# Teensy_3_2_Schematic.net
KiCad netlist of a schematic drawn in Altium Designer
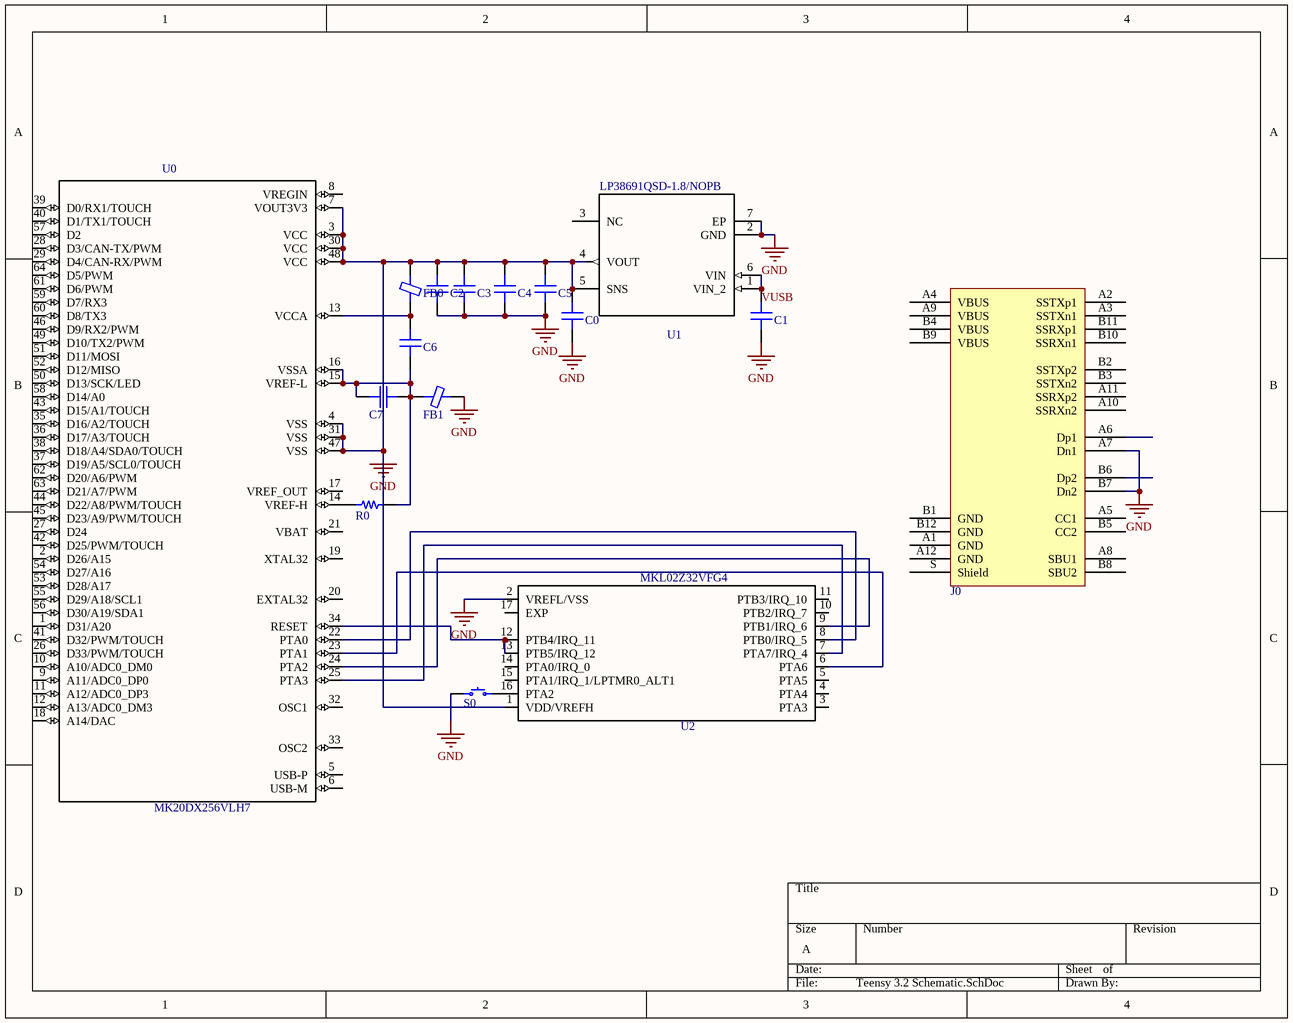
[diagram p0: Teensy 3.2 Schematic.SchDoc]

(export (version "E")
  (design (tool "Eeschema 10.0.6"))
  (components
    (comp (ref "C0")
      (value "2.2uF")
      (footprint "CAP 0201/0603")
      (description "CAP CER 2.2UF 10V X5R 0201")
      (fields
        (field (name "PART NUMBER") "GRM033R61A225KE47D")
        (field (name "MANUFACTURER") "Murata Electronics North America")
      )
      (libsource (lib "Celestial Library Database") (part "Capacitor"))
    )
    (comp (ref "C1")
      (value "2.2uF")
      (footprint "CAP 0201/0603")
      (description "CAP CER 2.2UF 10V X5R 0201")
      (fields
        (field (name "PART NUMBER") "GRM033R61A225KE47D")
        (field (name "MANUFACTURER") "Murata Electronics North America")
      )
      (libsource (lib "Celestial Library Database") (part "Capacitor"))
    )
    (comp (ref "C2")
      (value "2.2uF")
      (footprint "CAP 0201/0603")
      (description "CAP CER 2.2UF 10V X5R 0201")
      (fields
        (field (name "PART NUMBER") "GRM033R61A225KE47D")
        (field (name "MANUFACTURER") "Murata Electronics North America")
      )
      (libsource (lib "Celestial Library Database") (part "Capacitor"))
    )
    (comp (ref "C3")
      (value "0.1uF")
      (footprint "CAP 0402/1005")
      (description "CAP CER 0.1UF 6.3V X7R 0402")
      (fields
        (field (name "PART NUMBER") "GRM155R70J104KA01D")
        (field (name "MANUFACTURER") "Murata Electronics North America")
      )
      (libsource (lib "Celestial Library Database") (part "Capacitor"))
    )
    (comp (ref "C4")
      (value "0.1uF")
      (footprint "CAP 0402/1005")
      (description "CAP CER 0.1UF 6.3V X7R 0402")
      (fields
        (field (name "PART NUMBER") "GRM155R70J104KA01D")
        (field (name "MANUFACTURER") "Murata Electronics North America")
      )
      (libsource (lib "Celestial Library Database") (part "Capacitor"))
    )
    (comp (ref "C5")
      (value "0.1uF")
      (footprint "CAP 0402/1005")
      (description "CAP CER 0.1UF 6.3V X7R 0402")
      (fields
        (field (name "PART NUMBER") "GRM155R70J104KA01D")
        (field (name "MANUFACTURER") "Murata Electronics North America")
      )
      (libsource (lib "Celestial Library Database") (part "Capacitor"))
    )
    (comp (ref "C6")
      (value "2.2uF")
      (footprint "CAP 0201/0603")
      (description "CAP CER 2.2UF 10V X5R 0201")
      (fields
        (field (name "PART NUMBER") "GRM033R61A225KE47D")
        (field (name "MANUFACTURER") "Murata Electronics North America")
      )
      (libsource (lib "Celestial Library Database") (part "Capacitor"))
    )
    (comp (ref "C7")
      (value "0.1uF")
      (footprint "CAP 0402/1005")
      (description "CAP CER 0.1UF 6.3V X7R 0402")
      (fields
        (field (name "PART NUMBER") "GRM155R70J104KA01D")
        (field (name "MANUFACTURER") "Murata Electronics North America")
      )
      (libsource (lib "Celestial Library Database") (part "Capacitor"))
    )
    (comp (ref "FB0")
      (value "600 Ohm @ 100MHz")
      (footprint "FER 0201/0603")
      (description "FERRITE BEAD 600 OHM 0201 1LN")
      (fields
        (field (name "PART NUMBER") "BLM03AX601SN1D")
        (field (name "MANUFACTURER") "Murata Electronics North America")
      )
      (libsource (lib "Celestial Library Database") (part "Ferrite Chip"))
    )
    (comp (ref "FB1")
      (value "600 Ohm @ 100MHz")
      (footprint "FER 0201/0603")
      (description "FERRITE BEAD 600 OHM 0201 1LN")
      (fields
        (field (name "PART NUMBER") "BLM03AX601SN1D")
        (field (name "MANUFACTURER") "Murata Electronics North America")
      )
      (libsource (lib "Celestial Library Database") (part "Ferrite Chip"))
    )
    (comp (ref "J0")
      (value "USB C")
      (footprint "TE USB-C 2129691-1")
      (description "USB 3.1 TYPE C MID MOUNT HYBRID")
      (fields
        (field (name "PART NUMBER") "2129691-1")
        (field (name "MANUFACTURER") "TE Connectivity AMP Connectors")
      )
      (libsource (lib "Celestial Library Database") (part "USB 3.0 Type C"))
    )
    (comp (ref "R0")
      (value "470")
      (footprint "RES 0402/1005")
      (description "RES SMD 470 OHM 1% 1/10W 0402")
      (fields
        (field (name "PART NUMBER") "ERJ-2RKF4700X")
        (field (name "MANUFACTURER") "Panasonic Electronic Components")
      )
      (libsource (lib "Celestial Library Database") (part "Resistor"))
    )
    (comp (ref "S0")
      (value "FSMSMTR")
      (footprint "TE FSMSMTR")
      (description "SWITCH TACTILE SPST-NO 0.05A 24V")
      (fields (field (name "MANUFACTURER") "TE Connectivity Alcoswitch Switches"))
      (libsource (lib "Celestial Library Database") (part "SPST-NO 2 PIN"))
    )
    (comp (ref "U0")
      (value "MK20DX256VLH7")
      (footprint "QFP50P1200X1200X160-64N")
      (description "MCU 32-bit Kinetis K20 ARM Cortex M4 RISC 256KB Flash 1.8V/2.5V/3.3V 64-Pin LQFP Tray")
      (fields (field (name "MF") "NXP USA"))
      (libsource (lib "MK20DX256VLH7") (part "MK20DX256VLH7"))
    )
    (comp (ref "U1")
      (value "LP38691QSD-1.8/NOPB")
      (footprint "DFN300X300X80-7N")
      (description "500mA Low Dropout CMOS Linear egulators Stable with Ceramic Output Capacitors 6-WSON -40 to 125")
      (fields (field (name "MF") "Texas Instruments"))
      (libsource (lib "LP38691QSD-1.8_NOPB") (part "LP38691QSD-1.8/NOPB"))
    )
    (comp (ref "U2")
      (value "MKL02Z32VFG4")
      (footprint "QFN50P300X300X65-17N")
      (description "MCU 32-Bit KL02 ARM Cortex M0+ RISC 32KB Flash 1.8V/2.5V/3.3V 16-Pin QFN EP Tray")
      (fields (field (name "MF") "NXP USA"))
      (libsource (lib "MKL02Z32VFG4") (part "MKL02Z32VFG4"))
    )
  )
  (nets
    (net (code "1") (name "/VUSB") (class "Default")
      (node (ref "C1") (pin "1") (pinfunction "1_1") (pintype "passive"))
      (node (ref "U1") (pin "1") (pinfunction "VIN_2_1") (pintype "input"))
      (node (ref "U1") (pin "6") (pinfunction "VIN_6") (pintype "input"))
    )
    (net (code "2") (name "GND") (class "Default")
      (node (ref "C0") (pin "1") (pinfunction "1_1") (pintype "passive"))
      (node (ref "C0") (pin "2") (pinfunction "2_2") (pintype "passive"))
      (node (ref "C1") (pin "2") (pinfunction "2_2") (pintype "passive"))
      (node (ref "C2") (pin "1") (pinfunction "1_1") (pintype "passive"))
      (node (ref "C2") (pin "2") (pinfunction "2_2") (pintype "passive"))
      (node (ref "C3") (pin "1") (pinfunction "1_1") (pintype "passive"))
      (node (ref "C3") (pin "2") (pinfunction "2_2") (pintype "passive"))
      (node (ref "C4") (pin "1") (pinfunction "1_1") (pintype "passive"))
      (node (ref "C4") (pin "2") (pinfunction "2_2") (pintype "passive"))
      (node (ref "C5") (pin "1") (pinfunction "1_1") (pintype "passive"))
      (node (ref "C5") (pin "2") (pinfunction "2_2") (pintype "passive"))
      (node (ref "FB0") (pin "1") (pinfunction "1_1") (pintype "passive"))
      (node (ref "FB1") (pin "1") (pinfunction "1_1") (pintype "passive"))
      (node (ref "J0") (pin "A7") (pinfunction "Dn1_A7") (pintype "passive"))
      (node (ref "J0") (pin "B7") (pinfunction "Dn2_B7") (pintype "passive"))
      (node (ref "S0") (pin "1") (pinfunction "1_1") (pintype "passive"))
      (node (ref "U0") (pin "3") (pinfunction "VCC_3") (pintype "bidirectional"))
      (node (ref "U0") (pin "30") (pinfunction "VCC_30") (pintype "bidirectional"))
      (node (ref "U0") (pin "31") (pinfunction "VSS_31") (pintype "bidirectional"))
      (node (ref "U0") (pin "4") (pinfunction "VSS_4") (pintype "bidirectional"))
      (node (ref "U0") (pin "47") (pinfunction "VSS_47") (pintype "bidirectional"))
      (node (ref "U0") (pin "48") (pinfunction "VCC_48") (pintype "bidirectional"))
      (node (ref "U0") (pin "7") (pinfunction "VOUT3V3_7") (pintype "bidirectional"))
      (node (ref "U1") (pin "2") (pinfunction "GND_2") (pintype "passive"))
      (node (ref "U1") (pin "4") (pinfunction "VOUT_4") (pintype "output"))
      (node (ref "U1") (pin "5") (pinfunction "SNS_5") (pintype "passive"))
      (node (ref "U1") (pin "7") (pinfunction "EP_7") (pintype "passive"))
      (node (ref "U2") (pin "1") (pinfunction "VDD/VREFH_1") (pintype "power_in"))
      (node (ref "U2") (pin "2") (pinfunction "VREFL/VSS_2") (pintype "power_in"))
    )
    (net (code "3") (name "Net-(U0-PTA0)") (class "Default")
      (node (ref "U0") (pin "22") (pinfunction "PTA0_22") (pintype "bidirectional"))
      (node (ref "U2") (pin "8") (pinfunction "PTB0/IRQ_5_8") (pintype "bidirectional"))
    )
    (net (code "4") (name "Net-(U0-PTA1)") (class "Default")
      (node (ref "U0") (pin "23") (pinfunction "PTA1_23") (pintype "bidirectional"))
      (node (ref "U2") (pin "6") (pinfunction "PTA6_6") (pintype "bidirectional"))
    )
    (net (code "5") (name "Net-(U0-PTA2)") (class "Default")
      (node (ref "U0") (pin "24") (pinfunction "PTA2_24") (pintype "bidirectional"))
      (node (ref "U2") (pin "9") (pinfunction "PTB1/IRQ_6_9") (pintype "bidirectional"))
    )
    (net (code "6") (name "Net-(U0-PTA3)") (class "Default")
      (node (ref "U0") (pin "25") (pinfunction "PTA3_25") (pintype "bidirectional"))
      (node (ref "U2") (pin "7") (pinfunction "PTA7/IRQ_4_7") (pintype "bidirectional"))
    )
    (net (code "7") (name "Net-(U0-RESET)") (class "Default")
      (node (ref "U0") (pin "34") (pinfunction "RESET_34") (pintype "bidirectional"))
      (node (ref "U2") (pin "12") (pinfunction "PTB4/IRQ_11_12") (pintype "bidirectional"))
      (node (ref "U2") (pin "13") (pinfunction "PTB5/IRQ_12_13") (pintype "bidirectional"))
    )
    (net (code "8") (name "Net-(U0-VCCA)") (class "Default")
      (node (ref "C6") (pin "1") (pinfunction "1_1") (pintype "passive"))
      (node (ref "FB0") (pin "2") (pinfunction "2_2") (pintype "passive"))
      (node (ref "U0") (pin "13") (pinfunction "VCCA_13") (pintype "bidirectional"))
    )
    (net (code "9") (name "Net-(U0-VREF-H)") (class "Default")
      (node (ref "R0") (pin "2") (pinfunction "2_2") (pintype "passive"))
      (node (ref "U0") (pin "14") (pinfunction "VREF-H_14") (pintype "bidirectional"))
    )
    (net (code "10") (name "Net-(U0-VREF-L)") (class "Default")
      (node (ref "C6") (pin "2") (pinfunction "2_2") (pintype "passive"))
      (node (ref "C7") (pin "1") (pinfunction "1_1") (pintype "passive"))
      (node (ref "C7") (pin "2") (pinfunction "2_2") (pintype "passive"))
      (node (ref "FB1") (pin "2") (pinfunction "2_2") (pintype "passive"))
      (node (ref "R0") (pin "1") (pinfunction "1_1") (pintype "passive"))
      (node (ref "U0") (pin "15") (pinfunction "VREF-L_15") (pintype "bidirectional"))
      (node (ref "U0") (pin "16") (pinfunction "VSSA_16") (pintype "bidirectional"))
    )
    (net (code "11") (name "Net-(U2-PTA2)") (class "Default")
      (node (ref "S0") (pin "2") (pinfunction "2_2") (pintype "passive"))
      (node (ref "U2") (pin "16") (pinfunction "PTA2_16") (pintype "bidirectional"))
    )
    (net (code "12") (name "unconnected-(J0-CC1-PadA5)") (class "Default")
      (node (ref "J0") (pin "A5") (pinfunction "CC1_A5") (pintype "passive"))
    )
    (net (code "13") (name "unconnected-(J0-CC2-PadB5)") (class "Default")
      (node (ref "J0") (pin "B5") (pinfunction "CC2_B5") (pintype "passive"))
    )
    (net (code "14") (name "unconnected-(J0-Dp1-PadA6)") (class "Default")
      (node (ref "J0") (pin "A6") (pinfunction "Dp1_A6") (pintype "passive"))
    )
    (net (code "15") (name "unconnected-(J0-Dp2-PadB6)") (class "Default")
      (node (ref "J0") (pin "B6") (pinfunction "Dp2_B6") (pintype "passive"))
    )
    (net (code "16") (name "unconnected-(J0-GND-PadA1)") (class "Default")
      (node (ref "J0") (pin "A1") (pinfunction "GND_A1") (pintype "passive"))
    )
    (net (code "17") (name "unconnected-(J0-GND-PadA12)") (class "Default")
      (node (ref "J0") (pin "A12") (pinfunction "GND_A12") (pintype "passive"))
    )
    (net (code "18") (name "unconnected-(J0-GND-PadB1)") (class "Default")
      (node (ref "J0") (pin "B1") (pinfunction "GND_B1") (pintype "passive"))
    )
    (net (code "19") (name "unconnected-(J0-GND-PadB12)") (class "Default")
      (node (ref "J0") (pin "B12") (pinfunction "GND_B12") (pintype "passive"))
    )
    (net (code "20") (name "unconnected-(J0-SBU1-PadA8)") (class "Default")
      (node (ref "J0") (pin "A8") (pinfunction "SBU1_A8") (pintype "passive"))
    )
    (net (code "21") (name "unconnected-(J0-SBU2-PadB8)") (class "Default")
      (node (ref "J0") (pin "B8") (pinfunction "SBU2_B8") (pintype "passive"))
    )
    (net (code "22") (name "unconnected-(J0-SSRXn1-PadB10)") (class "Default")
      (node (ref "J0") (pin "B10") (pinfunction "SSRXn1_B10") (pintype "passive"))
    )
    (net (code "23") (name "unconnected-(J0-SSRXn2-PadA10)") (class "Default")
      (node (ref "J0") (pin "A10") (pinfunction "SSRXn2_A10") (pintype "passive"))
    )
    (net (code "24") (name "unconnected-(J0-SSRXp1-PadB11)") (class "Default")
      (node (ref "J0") (pin "B11") (pinfunction "SSRXp1_B11") (pintype "passive"))
    )
    (net (code "25") (name "unconnected-(J0-SSRXp2-PadA11)") (class "Default")
      (node (ref "J0") (pin "A11") (pinfunction "SSRXp2_A11") (pintype "passive"))
    )
    (net (code "26") (name "unconnected-(J0-SSTXn1-PadA3)") (class "Default")
      (node (ref "J0") (pin "A3") (pinfunction "SSTXn1_A3") (pintype "passive"))
    )
    (net (code "27") (name "unconnected-(J0-SSTXn2-PadB3)") (class "Default")
      (node (ref "J0") (pin "B3") (pinfunction "SSTXn2_B3") (pintype "passive"))
    )
    (net (code "28") (name "unconnected-(J0-SSTXp1-PadA2)") (class "Default")
      (node (ref "J0") (pin "A2") (pinfunction "SSTXp1_A2") (pintype "passive"))
    )
    (net (code "29") (name "unconnected-(J0-SSTXp2-PadB2)") (class "Default")
      (node (ref "J0") (pin "B2") (pinfunction "SSTXp2_B2") (pintype "passive"))
    )
    (net (code "30") (name "unconnected-(J0-Shield-PadS)") (class "Default")
      (node (ref "J0") (pin "S") (pinfunction "Shield_S") (pintype "passive"))
    )
    (net (code "31") (name "unconnected-(J0-VBUS-PadA4)") (class "Default")
      (node (ref "J0") (pin "A4") (pinfunction "VBUS_A4") (pintype "passive"))
    )
    (net (code "32") (name "unconnected-(J0-VBUS-PadA9)") (class "Default")
      (node (ref "J0") (pin "A9") (pinfunction "VBUS_A9") (pintype "passive"))
    )
    (net (code "33") (name "unconnected-(J0-VBUS-PadB4)") (class "Default")
      (node (ref "J0") (pin "B4") (pinfunction "VBUS_B4") (pintype "passive"))
    )
    (net (code "34") (name "unconnected-(J0-VBUS-PadB9)") (class "Default")
      (node (ref "J0") (pin "B9") (pinfunction "VBUS_B9") (pintype "passive"))
    )
    (net (code "35") (name "unconnected-(U0-A10{slash}ADC0_DM0-Pad10)") (class "Default")
      (node (ref "U0") (pin "10") (pinfunction "A10/ADC0_DM0_10") (pintype "bidirectional"))
    )
    (net (code "36") (name "unconnected-(U0-A11{slash}ADC0_DP0-Pad9)") (class "Default")
      (node (ref "U0") (pin "9") (pinfunction "A11/ADC0_DP0_9") (pintype "bidirectional"))
    )
    (net (code "37") (name "unconnected-(U0-A12{slash}ADC0_DP3-Pad11)") (class "Default")
      (node (ref "U0") (pin "11") (pinfunction "A12/ADC0_DP3_11") (pintype "bidirectional"))
    )
    (net (code "38") (name "unconnected-(U0-A13{slash}ADC0_DM3-Pad12)") (class "Default")
      (node (ref "U0") (pin "12") (pinfunction "A13/ADC0_DM3_12") (pintype "bidirectional"))
    )
    (net (code "39") (name "unconnected-(U0-A14{slash}DAC-Pad18)") (class "Default")
      (node (ref "U0") (pin "18") (pinfunction "A14/DAC_18") (pintype "bidirectional"))
    )
    (net (code "40") (name "unconnected-(U0-D0{slash}RX1{slash}TOUCH-Pad39)") (class "Default")
      (node (ref "U0") (pin "39") (pinfunction "D0/RX1/TOUCH_39") (pintype "bidirectional"))
    )
    (net (code "41") (name "unconnected-(U0-D1{slash}TX1{slash}TOUCH-Pad40)") (class "Default")
      (node (ref "U0") (pin "40") (pinfunction "D1/TX1/TOUCH_40") (pintype "bidirectional"))
    )
    (net (code "42") (name "unconnected-(U0-D2-Pad57)") (class "Default")
      (node (ref "U0") (pin "57") (pinfunction "D2_57") (pintype "bidirectional"))
    )
    (net (code "43") (name "unconnected-(U0-D3{slash}CAN-TX{slash}PWM-Pad28)") (class "Default")
      (node (ref "U0") (pin "28") (pinfunction "D3/CAN-TX/PWM_28") (pintype "bidirectional"))
    )
    (net (code "44") (name "unconnected-(U0-D4{slash}CAN-RX{slash}PWM-Pad29)") (class "Default")
      (node (ref "U0") (pin "29") (pinfunction "D4/CAN-RX/PWM_29") (pintype "bidirectional"))
    )
    (net (code "45") (name "unconnected-(U0-D5{slash}PWM-Pad64)") (class "Default")
      (node (ref "U0") (pin "64") (pinfunction "D5/PWM_64") (pintype "bidirectional"))
    )
    (net (code "46") (name "unconnected-(U0-D6{slash}PWM-Pad61)") (class "Default")
      (node (ref "U0") (pin "61") (pinfunction "D6/PWM_61") (pintype "bidirectional"))
    )
    (net (code "47") (name "unconnected-(U0-D7{slash}RX3-Pad59)") (class "Default")
      (node (ref "U0") (pin "59") (pinfunction "D7/RX3_59") (pintype "bidirectional"))
    )
    (net (code "48") (name "unconnected-(U0-D8{slash}TX3-Pad60)") (class "Default")
      (node (ref "U0") (pin "60") (pinfunction "D8/TX3_60") (pintype "bidirectional"))
    )
    (net (code "49") (name "unconnected-(U0-D9{slash}RX2{slash}PWM-Pad46)") (class "Default")
      (node (ref "U0") (pin "46") (pinfunction "D9/RX2/PWM_46") (pintype "bidirectional"))
    )
    (net (code "50") (name "unconnected-(U0-D10{slash}TX2{slash}PWM-Pad49)") (class "Default")
      (node (ref "U0") (pin "49") (pinfunction "D10/TX2/PWM_49") (pintype "bidirectional"))
    )
    (net (code "51") (name "unconnected-(U0-D11{slash}MOSI-Pad51)") (class "Default")
      (node (ref "U0") (pin "51") (pinfunction "D11/MOSI_51") (pintype "bidirectional"))
    )
    (net (code "52") (name "unconnected-(U0-D12{slash}MISO-Pad52)") (class "Default")
      (node (ref "U0") (pin "52") (pinfunction "D12/MISO_52") (pintype "bidirectional"))
    )
    (net (code "53") (name "unconnected-(U0-D13{slash}SCK{slash}LED-Pad50)") (class "Default")
      (node (ref "U0") (pin "50") (pinfunction "D13/SCK/LED_50") (pintype "bidirectional"))
    )
    (net (code "54") (name "unconnected-(U0-D14{slash}A0-Pad58)") (class "Default")
      (node (ref "U0") (pin "58") (pinfunction "D14/A0_58") (pintype "bidirectional"))
    )
    (net (code "55") (name "unconnected-(U0-D15{slash}A1{slash}TOUCH-Pad43)") (class "Default")
      (node (ref "U0") (pin "43") (pinfunction "D15/A1/TOUCH_43") (pintype "bidirectional"))
    )
    (net (code "56") (name "unconnected-(U0-D16{slash}A2{slash}TOUCH-Pad35)") (class "Default")
      (node (ref "U0") (pin "35") (pinfunction "D16/A2/TOUCH_35") (pintype "bidirectional"))
    )
    (net (code "57") (name "unconnected-(U0-D17{slash}A3{slash}TOUCH-Pad36)") (class "Default")
      (node (ref "U0") (pin "36") (pinfunction "D17/A3/TOUCH_36") (pintype "bidirectional"))
    )
    (net (code "58") (name "unconnected-(U0-D18{slash}A4{slash}SDA0{slash}TOUCH-Pad38)") (class "Default")
      (node (ref "U0") (pin "38") (pinfunction "D18/A4/SDA0/TOUCH_38") (pintype "bidirectional"))
    )
    (net (code "59") (name "unconnected-(U0-D19{slash}A5{slash}SCL0{slash}TOUCH-Pad37)") (class "Default")
      (node (ref "U0") (pin "37") (pinfunction "D19/A5/SCL0/TOUCH_37") (pintype "bidirectional"))
    )
    (net (code "60") (name "unconnected-(U0-D20{slash}A6{slash}PWM-Pad62)") (class "Default")
      (node (ref "U0") (pin "62") (pinfunction "D20/A6/PWM_62") (pintype "bidirectional"))
    )
    (net (code "61") (name "unconnected-(U0-D21{slash}A7{slash}PWM-Pad63)") (class "Default")
      (node (ref "U0") (pin "63") (pinfunction "D21/A7/PWM_63") (pintype "bidirectional"))
    )
    (net (code "62") (name "unconnected-(U0-D22{slash}A8{slash}PWM{slash}TOUCH-Pad44)") (class "Default")
      (node (ref "U0") (pin "44") (pinfunction "D22/A8/PWM/TOUCH_44") (pintype "bidirectional"))
    )
    (net (code "63") (name "unconnected-(U0-D23{slash}A9{slash}PWM{slash}TOUCH-Pad45)") (class "Default")
      (node (ref "U0") (pin "45") (pinfunction "D23/A9/PWM/TOUCH_45") (pintype "bidirectional"))
    )
    (net (code "64") (name "unconnected-(U0-D24-Pad27)") (class "Default")
      (node (ref "U0") (pin "27") (pinfunction "D24_27") (pintype "bidirectional"))
    )
    (net (code "65") (name "unconnected-(U0-D25{slash}PWM{slash}TOUCH-Pad42)") (class "Default")
      (node (ref "U0") (pin "42") (pinfunction "D25/PWM/TOUCH_42") (pintype "bidirectional"))
    )
    (net (code "66") (name "unconnected-(U0-D26{slash}A15-Pad2)") (class "Default")
      (node (ref "U0") (pin "2") (pinfunction "D26/A15_2") (pintype "bidirectional"))
    )
    (net (code "67") (name "unconnected-(U0-D27{slash}A16-Pad54)") (class "Default")
      (node (ref "U0") (pin "54") (pinfunction "D27/A16_54") (pintype "bidirectional"))
    )
    (net (code "68") (name "unconnected-(U0-D28{slash}A17-Pad53)") (class "Default")
      (node (ref "U0") (pin "53") (pinfunction "D28/A17_53") (pintype "bidirectional"))
    )
    (net (code "69") (name "unconnected-(U0-D29{slash}A18{slash}SCL1-Pad55)") (class "Default")
      (node (ref "U0") (pin "55") (pinfunction "D29/A18/SCL1_55") (pintype "bidirectional"))
    )
    (net (code "70") (name "unconnected-(U0-D30{slash}A19{slash}SDA1-Pad56)") (class "Default")
      (node (ref "U0") (pin "56") (pinfunction "D30/A19/SDA1_56") (pintype "bidirectional"))
    )
    (net (code "71") (name "unconnected-(U0-D31{slash}A20-Pad1)") (class "Default")
      (node (ref "U0") (pin "1") (pinfunction "D31/A20_1") (pintype "bidirectional"))
    )
    (net (code "72") (name "unconnected-(U0-D32{slash}PWM{slash}TOUCH-Pad41)") (class "Default")
      (node (ref "U0") (pin "41") (pinfunction "D32/PWM/TOUCH_41") (pintype "bidirectional"))
    )
    (net (code "73") (name "unconnected-(U0-D33{slash}PWM{slash}TOUCH-Pad26)") (class "Default")
      (node (ref "U0") (pin "26") (pinfunction "D33/PWM/TOUCH_26") (pintype "bidirectional"))
    )
    (net (code "74") (name "unconnected-(U0-EXTAL32-Pad20)") (class "Default")
      (node (ref "U0") (pin "20") (pinfunction "EXTAL32_20") (pintype "bidirectional"))
    )
    (net (code "75") (name "unconnected-(U0-OSC1-Pad32)") (class "Default")
      (node (ref "U0") (pin "32") (pinfunction "OSC1_32") (pintype "bidirectional"))
    )
    (net (code "76") (name "unconnected-(U0-OSC2-Pad33)") (class "Default")
      (node (ref "U0") (pin "33") (pinfunction "OSC2_33") (pintype "bidirectional"))
    )
    (net (code "77") (name "unconnected-(U0-USB-M-Pad6)") (class "Default")
      (node (ref "U0") (pin "6") (pinfunction "USB-M_6") (pintype "bidirectional"))
    )
    (net (code "78") (name "unconnected-(U0-USB-P-Pad5)") (class "Default")
      (node (ref "U0") (pin "5") (pinfunction "USB-P_5") (pintype "bidirectional"))
    )
    (net (code "79") (name "unconnected-(U0-VBAT-Pad21)") (class "Default")
      (node (ref "U0") (pin "21") (pinfunction "VBAT_21") (pintype "bidirectional"))
    )
    (net (code "80") (name "unconnected-(U0-VREF_OUT-Pad17)") (class "Default")
      (node (ref "U0") (pin "17") (pinfunction "VREF_OUT_17") (pintype "bidirectional"))
    )
    (net (code "81") (name "unconnected-(U0-VREGIN-Pad8)") (class "Default")
      (node (ref "U0") (pin "8") (pinfunction "VREGIN_8") (pintype "bidirectional"))
    )
    (net (code "82") (name "unconnected-(U0-XTAL32-Pad19)") (class "Default")
      (node (ref "U0") (pin "19") (pinfunction "XTAL32_19") (pintype "bidirectional"))
    )
    (net (code "83") (name "unconnected-(U1-NC-Pad3)") (class "Default")
      (node (ref "U1") (pin "3") (pinfunction "NC_3") (pintype "passive"))
    )
    (net (code "84") (name "unconnected-(U2-EXP-Pad17)") (class "Default")
      (node (ref "U2") (pin "17") (pinfunction "EXP_17") (pintype "power_in"))
    )
    (net (code "85") (name "unconnected-(U2-PTA0{slash}IRQ_0-Pad14)") (class "Default")
      (node (ref "U2") (pin "14") (pinfunction "PTA0/IRQ_0_14") (pintype "bidirectional"))
    )
    (net (code "86") (name "unconnected-(U2-PTA1{slash}IRQ_1{slash}LPTMR0_ALT1-Pad15)") (class "Default")
      (node (ref "U2") (pin "15") (pinfunction "PTA1/IRQ_1/LPTMR0_ALT1_15") (pintype "bidirectional"))
    )
    (net (code "87") (name "unconnected-(U2-PTA3-Pad3)") (class "Default")
      (node (ref "U2") (pin "3") (pinfunction "PTA3_3") (pintype "bidirectional"))
    )
    (net (code "88") (name "unconnected-(U2-PTA4-Pad4)") (class "Default")
      (node (ref "U2") (pin "4") (pinfunction "PTA4_4") (pintype "bidirectional"))
    )
    (net (code "89") (name "unconnected-(U2-PTA5-Pad5)") (class "Default")
      (node (ref "U2") (pin "5") (pinfunction "PTA5_5") (pintype "bidirectional"))
    )
    (net (code "90") (name "unconnected-(U2-PTB2{slash}IRQ_7-Pad10)") (class "Default")
      (node (ref "U2") (pin "10") (pinfunction "PTB2/IRQ_7_10") (pintype "bidirectional"))
    )
    (net (code "91") (name "unconnected-(U2-PTB3{slash}IRQ_10-Pad11)") (class "Default")
      (node (ref "U2") (pin "11") (pinfunction "PTB3/IRQ_10_11") (pintype "bidirectional"))
    )
  )
)
